# main.net
KiCad netlist of a schematic drawn in Altium Designer
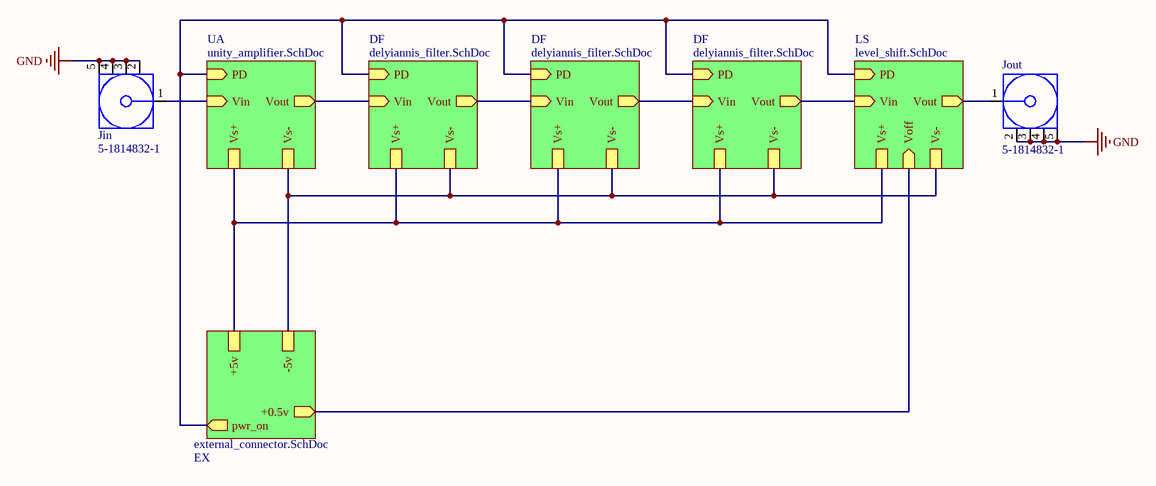
[diagram p0: main.SchDoc]

(export (version "E")
  (design (tool "Eeschema 10.0.6"))
  (components
    (comp (ref "Jin")
      (value "5-1814832-1")
      (footprint "TECO-5-1814832-1_V")
      (fields (field (name "MANUFACTURER") "TE Connectivity"))
      (libsource (lib "Altium Content Vault") (part "CN-S-4F-RF5"))
    )
    (comp (ref "Jout")
      (value "5-1814832-1")
      (footprint "TECO-5-1814832-1_V")
      (fields (field (name "MANUFACTURER") "TE Connectivity"))
      (libsource (lib "Altium Content Vault") (part "CN-S-4F-RF5"))
    )
  )
  (nets
    (net (code "4") (name "/Vin") (class "Default")
      (node (ref "Jin") (pin "1") (pinfunction "1_1") (pintype "passive"))
    )
    (net (code "5") (name "/Vout") (class "Default")
      (node (ref "Jout") (pin "1") (pinfunction "1_1") (pintype "passive"))
    )
    (net (code "11") (name "GND") (class "Default")
      (node (ref "Jin") (pin "2") (pinfunction "2_2") (pintype "passive"))
      (node (ref "Jin") (pin "3") (pinfunction "3_3") (pintype "passive"))
      (node (ref "Jin") (pin "4") (pinfunction "4_4") (pintype "passive"))
      (node (ref "Jin") (pin "5") (pinfunction "5_5") (pintype "passive"))
      (node (ref "Jout") (pin "2") (pinfunction "2_2") (pintype "passive"))
      (node (ref "Jout") (pin "3") (pinfunction "3_3") (pintype "passive"))
      (node (ref "Jout") (pin "4") (pinfunction "4_4") (pintype "passive"))
      (node (ref "Jout") (pin "5") (pinfunction "5_5") (pintype "passive"))
    )
  )
)
